# Sch1r2_1.net
KiCad netlist of a schematic drawn in EAGLE
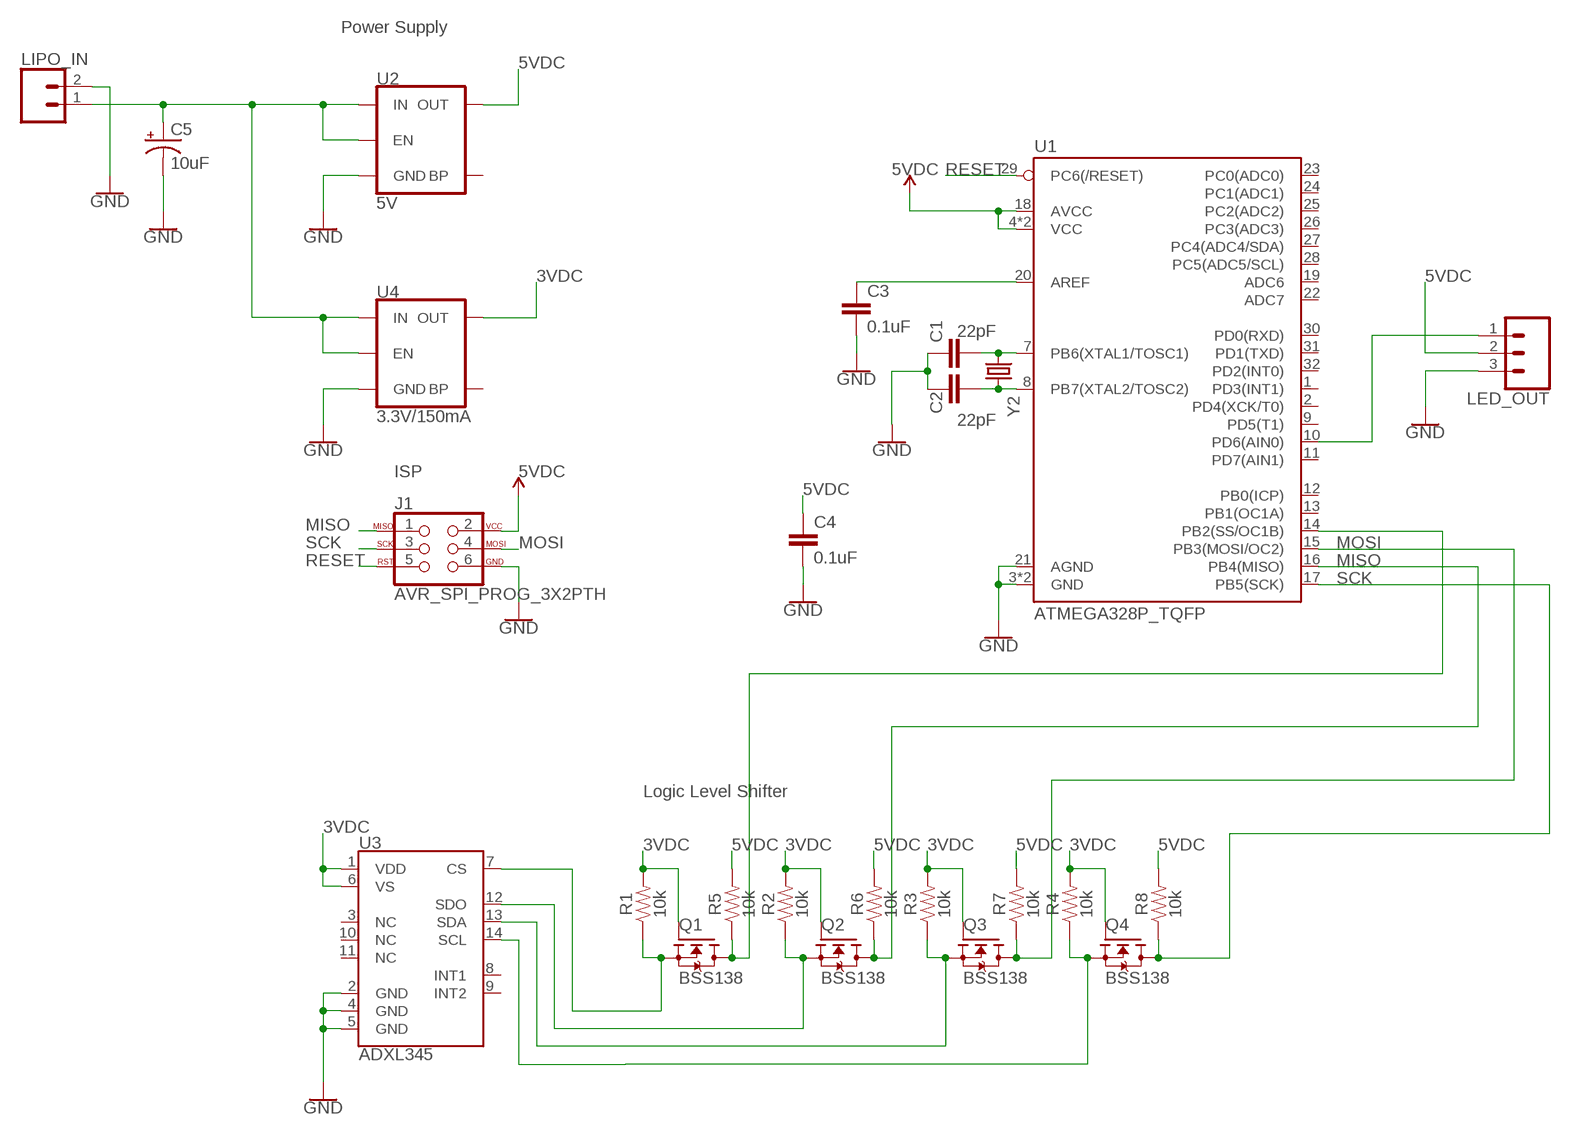
[diagram p0: schematic, sheet 1]

(export (version "E")
  (design (tool "Eeschema 10.0.6"))
  (components
    (comp (ref "C1")
      (value "22pF")
      (footprint "eagle-import:0603")
      (libsource (lib "eagle-import") (part "22PF-0603-50V-5%"))
    )
    (comp (ref "C2")
      (value "22pF")
      (footprint "eagle-import:0603")
      (libsource (lib "eagle-import") (part "22PF-0603-50V-5%"))
    )
    (comp (ref "C3")
      (value "0.1uF")
      (footprint "eagle-import:0402")
      (libsource (lib "eagle-import") (part "0.1UF-0402-16V-10%"))
    )
    (comp (ref "C4")
      (value "0.1uF")
      (footprint "eagle-import:0402")
      (libsource (lib "eagle-import") (part "0.1UF-0402-16V-10%"))
    )
    (comp (ref "C5")
      (value "10uF")
      (footprint "eagle-import:0603-POLAR")
      (libsource (lib "eagle-import") (part "10UF-POLAR-0603-6.3V-20%(TANT)"))
    )
    (comp (ref "J1")
      (value "AVR_SPI_PROG_3X2PTH")
      (footprint "eagle-import:2X3")
      (libsource (lib "eagle-import") (part "AVR_SPI_PROG_3X2PTH"))
    )
    (comp (ref "LED_OUT")
      (value "CONN_03LOCK_LONGPADS")
      (footprint "eagle-import:1X03_LOCK_LONGPADS")
      (libsource (lib "eagle-import") (part "CONN_03LOCK_LONGPADS"))
    )
    (comp (ref "LIPO_IN")
      (value "CONN_02PTH3")
      (footprint "eagle-import:1X02_LONGPADS")
      (libsource (lib "eagle-import") (part "CONN_02PTH3"))
    )
    (comp (ref "Q1")
      (value "BSS138")
      (footprint "eagle-import:SOT23")
      (fields (field (name "MF") "Fairchild"))
      (libsource (lib "eagle-import") (part "BSS138"))
    )
    (comp (ref "Q2")
      (value "BSS138")
      (footprint "eagle-import:SOT23")
      (fields (field (name "MF") "Fairchild"))
      (libsource (lib "eagle-import") (part "BSS138"))
    )
    (comp (ref "Q3")
      (value "BSS138")
      (footprint "eagle-import:SOT23")
      (fields (field (name "MF") "Fairchild"))
      (libsource (lib "eagle-import") (part "BSS138"))
    )
    (comp (ref "Q4")
      (value "BSS138")
      (footprint "eagle-import:SOT23")
      (fields (field (name "MF") "Fairchild"))
      (libsource (lib "eagle-import") (part "BSS138"))
    )
    (comp (ref "R1")
      (value "10k")
      (footprint "eagle-import:0402")
      (libsource (lib "eagle-import") (part "10KOHM-0402-1/16W-1%"))
    )
    (comp (ref "R2")
      (value "10k")
      (footprint "eagle-import:0402")
      (libsource (lib "eagle-import") (part "10KOHM-0402-1/16W-1%"))
    )
    (comp (ref "R3")
      (value "10k")
      (footprint "eagle-import:0402")
      (libsource (lib "eagle-import") (part "10KOHM-0402-1/16W-1%"))
    )
    (comp (ref "R4")
      (value "10k")
      (footprint "eagle-import:0402")
      (libsource (lib "eagle-import") (part "10KOHM-0402-1/16W-1%"))
    )
    (comp (ref "R5")
      (value "10k")
      (footprint "eagle-import:0402")
      (libsource (lib "eagle-import") (part "10KOHM-0402-1/16W-1%"))
    )
    (comp (ref "R6")
      (value "10k")
      (footprint "eagle-import:0402")
      (libsource (lib "eagle-import") (part "10KOHM-0402-1/16W-1%"))
    )
    (comp (ref "R7")
      (value "10k")
      (footprint "eagle-import:0402")
      (libsource (lib "eagle-import") (part "10KOHM-0402-1/16W-1%"))
    )
    (comp (ref "R8")
      (value "10k")
      (footprint "eagle-import:0402")
      (libsource (lib "eagle-import") (part "10KOHM-0402-1/16W-1%"))
    )
    (comp (ref "U1")
      (value "ATMEGA328P_TQFP")
      (footprint "eagle-import:TQFP32-08")
      (libsource (lib "eagle-import") (part "ATMEGA328P_TQFP"))
    )
    (comp (ref "U2")
      (value "5V")
      (footprint "eagle-import:SOT23-5")
      (libsource (lib "eagle-import") (part "V_REG_MIC52055V"))
    )
    (comp (ref "U3")
      (value "ADXL345")
      (footprint "eagle-import:LGA-14")
      (libsource (lib "eagle-import") (part "ADXL345"))
    )
    (comp (ref "U4")
      (value "3.3V/150mA")
      (footprint "eagle-import:SOT23-5")
      (libsource (lib "eagle-import") (part "V_REG_MIC52053.3V"))
    )
    (comp (ref "Y2")
      (value "CRYSTALPTH-HC49UV")
      (footprint "eagle-import:HC49U")
      (libsource (lib "eagle-import") (part "CRYSTALPTH-HC49UV"))
    )
  )
  (nets
    (net (code "1") (name "/3VDC") (class "Default")
      (node (ref "Q1") (pin "1") (pinfunction "G_1") (pintype "passive"))
      (node (ref "Q2") (pin "1") (pinfunction "G_1") (pintype "passive"))
      (node (ref "Q3") (pin "1") (pinfunction "G_1") (pintype "passive"))
      (node (ref "Q4") (pin "1") (pinfunction "G_1") (pintype "passive"))
      (node (ref "R1") (pin "2") (pinfunction "2_2") (pintype "passive"))
      (node (ref "R2") (pin "2") (pinfunction "2_2") (pintype "passive"))
      (node (ref "R3") (pin "2") (pinfunction "2_2") (pintype "passive"))
      (node (ref "R4") (pin "2") (pinfunction "2_2") (pintype "passive"))
      (node (ref "U3") (pin "1") (pinfunction "VDD_1") (pintype "bidirectional"))
      (node (ref "U3") (pin "6") (pinfunction "VS_6") (pintype "bidirectional"))
      (node (ref "U4") (pin "5") (pinfunction "OUT_5") (pintype "passive"))
    )
    (net (code "2") (name "/MISO") (class "Default")
      (node (ref "J1") (pin "1") (pinfunction "1_1") (pintype "passive"))
      (node (ref "Q2") (pin "3") (pinfunction "D_3") (pintype "passive"))
      (node (ref "R6") (pin "1") (pinfunction "1_1") (pintype "passive"))
      (node (ref "U1") (pin "16") (pinfunction "PB4(MISO)_16") (pintype "bidirectional"))
    )
    (net (code "3") (name "/MOSI") (class "Default")
      (node (ref "J1") (pin "4") (pinfunction "4_4") (pintype "passive"))
      (node (ref "Q3") (pin "3") (pinfunction "D_3") (pintype "passive"))
      (node (ref "R7") (pin "1") (pinfunction "1_1") (pintype "passive"))
      (node (ref "U1") (pin "15") (pinfunction "PB3(MOSI/OC2)_15") (pintype "bidirectional"))
    )
    (net (code "4") (name "/RESET") (class "Default")
      (node (ref "J1") (pin "5") (pinfunction "5_5") (pintype "passive"))
      (node (ref "U1") (pin "29") (pinfunction "PC6(/RESET)_29") (pintype "bidirectional"))
    )
    (net (code "5") (name "/SCK") (class "Default")
      (node (ref "J1") (pin "3") (pinfunction "3_3") (pintype "passive"))
      (node (ref "Q4") (pin "3") (pinfunction "D_3") (pintype "passive"))
      (node (ref "R8") (pin "1") (pinfunction "1_1") (pintype "passive"))
      (node (ref "U1") (pin "17") (pinfunction "PB5(SCK)_17") (pintype "bidirectional"))
    )
    (net (code "6") (name "GND") (class "Default")
      (node (ref "C1") (pin "1") (pinfunction "1_1") (pintype "passive"))
      (node (ref "C2") (pin "1") (pinfunction "1_1") (pintype "passive"))
      (node (ref "C3") (pin "2") (pinfunction "2_2") (pintype "passive"))
      (node (ref "C4") (pin "2") (pinfunction "2_2") (pintype "passive"))
      (node (ref "C5") (pin "-") (pinfunction "-_-") (pintype "passive"))
      (node (ref "J1") (pin "6") (pinfunction "6_6") (pintype "passive"))
      (node (ref "LED_OUT") (pin "3") (pinfunction "3_3") (pintype "passive"))
      (node (ref "LIPO_IN") (pin "2") (pinfunction "2_2") (pintype "passive"))
      (node (ref "U1") (pin "21") (pinfunction "AGND_21") (pintype "bidirectional"))
      (node (ref "U1") (pin "3") (pinfunction "GND_3") (pintype "bidirectional"))
      (node (ref "U1") (pin "5") (pinfunction "GND_5") (pintype "bidirectional"))
      (node (ref "U2") (pin "2") (pinfunction "GND_2") (pintype "input"))
      (node (ref "U3") (pin "2") (pinfunction "GND_2") (pintype "bidirectional"))
      (node (ref "U3") (pin "4") (pinfunction "GND_4") (pintype "bidirectional"))
      (node (ref "U3") (pin "5") (pinfunction "GND_5") (pintype "bidirectional"))
      (node (ref "U4") (pin "2") (pinfunction "GND_2") (pintype "input"))
    )
    (net (code "7") (name "Net-(Q1-D)") (class "Default")
      (node (ref "Q1") (pin "3") (pinfunction "D_3") (pintype "passive"))
      (node (ref "R5") (pin "1") (pinfunction "1_1") (pintype "passive"))
      (node (ref "U1") (pin "14") (pinfunction "PB2(SS/OC1B)_14") (pintype "bidirectional"))
    )
    (net (code "8") (name "Net-(Q1-S)") (class "Default")
      (node (ref "Q1") (pin "2") (pinfunction "S_2") (pintype "passive"))
      (node (ref "R1") (pin "1") (pinfunction "1_1") (pintype "passive"))
      (node (ref "U3") (pin "7") (pinfunction "CS_7") (pintype "bidirectional"))
    )
    (net (code "9") (name "Net-(Q2-S)") (class "Default")
      (node (ref "Q2") (pin "2") (pinfunction "S_2") (pintype "passive"))
      (node (ref "R2") (pin "1") (pinfunction "1_1") (pintype "passive"))
      (node (ref "U3") (pin "12") (pinfunction "SDO_12") (pintype "bidirectional"))
    )
    (net (code "10") (name "Net-(Q3-S)") (class "Default")
      (node (ref "Q3") (pin "2") (pinfunction "S_2") (pintype "passive"))
      (node (ref "R3") (pin "1") (pinfunction "1_1") (pintype "passive"))
      (node (ref "U3") (pin "13") (pinfunction "SDA_13") (pintype "bidirectional"))
    )
    (net (code "11") (name "Net-(Q4-S)") (class "Default")
      (node (ref "Q4") (pin "2") (pinfunction "S_2") (pintype "passive"))
      (node (ref "R4") (pin "1") (pinfunction "1_1") (pintype "passive"))
      (node (ref "U3") (pin "14") (pinfunction "SCL_14") (pintype "bidirectional"))
    )
    (net (code "12") (name "Net-(U1-AREF)") (class "Default")
      (node (ref "C3") (pin "1") (pinfunction "1_1") (pintype "passive"))
      (node (ref "U1") (pin "20") (pinfunction "AREF_20") (pintype "bidirectional"))
    )
    (net (code "13") (name "Net-(U1-PB6(XTAL1{slash}TOSC1))") (class "Default")
      (node (ref "C1") (pin "2") (pinfunction "2_2") (pintype "passive"))
      (node (ref "U1") (pin "7") (pinfunction "PB6(XTAL1/TOSC1)_7") (pintype "bidirectional"))
      (node (ref "Y2") (pin "2") (pinfunction "2_2") (pintype "passive"))
    )
    (net (code "14") (name "Net-(U1-PB7(XTAL2{slash}TOSC2))") (class "Default")
      (node (ref "C2") (pin "2") (pinfunction "2_2") (pintype "passive"))
      (node (ref "U1") (pin "8") (pinfunction "PB7(XTAL2/TOSC2)_8") (pintype "bidirectional"))
      (node (ref "Y2") (pin "1") (pinfunction "1_1") (pintype "passive"))
    )
    (net (code "15") (name "Net-(U1-PD6(AIN0))") (class "Default")
      (node (ref "LED_OUT") (pin "1") (pinfunction "1_1") (pintype "passive"))
      (node (ref "U1") (pin "10") (pinfunction "PD6(AIN0)_10") (pintype "bidirectional"))
    )
    (net (code "16") (name "Net-(U2-EN)") (class "Default")
      (node (ref "C5") (pin "+") (pinfunction "+_+") (pintype "passive"))
      (node (ref "LIPO_IN") (pin "1") (pinfunction "1_1") (pintype "passive"))
      (node (ref "U2") (pin "1") (pinfunction "IN_1") (pintype "input"))
      (node (ref "U2") (pin "3") (pinfunction "EN_3") (pintype "input"))
      (node (ref "U4") (pin "1") (pinfunction "IN_1") (pintype "input"))
      (node (ref "U4") (pin "3") (pinfunction "EN_3") (pintype "input"))
    )
    (net (code "17") (name "VCC") (class "Default")
      (node (ref "C4") (pin "1") (pinfunction "1_1") (pintype "passive"))
      (node (ref "J1") (pin "2") (pinfunction "2_2") (pintype "passive"))
      (node (ref "LED_OUT") (pin "2") (pinfunction "2_2") (pintype "passive"))
      (node (ref "R5") (pin "2") (pinfunction "2_2") (pintype "passive"))
      (node (ref "R6") (pin "2") (pinfunction "2_2") (pintype "passive"))
      (node (ref "R7") (pin "2") (pinfunction "2_2") (pintype "passive"))
      (node (ref "R8") (pin "2") (pinfunction "2_2") (pintype "passive"))
      (node (ref "U1") (pin "18") (pinfunction "AVCC_18") (pintype "bidirectional"))
      (node (ref "U1") (pin "4") (pinfunction "VCC_4") (pintype "bidirectional"))
      (node (ref "U1") (pin "6") (pinfunction "VCC_6") (pintype "bidirectional"))
      (node (ref "U2") (pin "5") (pinfunction "OUT_5") (pintype "passive"))
    )
    (net (code "18") (name "unconnected-(U1-ADC6-Pad19)") (class "Default")
      (node (ref "U1") (pin "19") (pinfunction "ADC6_19") (pintype "bidirectional"))
    )
    (net (code "19") (name "unconnected-(U1-ADC7-Pad22)") (class "Default")
      (node (ref "U1") (pin "22") (pinfunction "ADC7_22") (pintype "bidirectional"))
    )
    (net (code "20") (name "unconnected-(U1-PB0(ICP)-Pad12)") (class "Default")
      (node (ref "U1") (pin "12") (pinfunction "PB0(ICP)_12") (pintype "bidirectional"))
    )
    (net (code "21") (name "unconnected-(U1-PB1(OC1A)-Pad13)") (class "Default")
      (node (ref "U1") (pin "13") (pinfunction "PB1(OC1A)_13") (pintype "bidirectional"))
    )
    (net (code "22") (name "unconnected-(U1-PC0(ADC0)-Pad23)") (class "Default")
      (node (ref "U1") (pin "23") (pinfunction "PC0(ADC0)_23") (pintype "bidirectional"))
    )
    (net (code "23") (name "unconnected-(U1-PC1(ADC1)-Pad24)") (class "Default")
      (node (ref "U1") (pin "24") (pinfunction "PC1(ADC1)_24") (pintype "bidirectional"))
    )
    (net (code "24") (name "unconnected-(U1-PC2(ADC2)-Pad25)") (class "Default")
      (node (ref "U1") (pin "25") (pinfunction "PC2(ADC2)_25") (pintype "bidirectional"))
    )
    (net (code "25") (name "unconnected-(U1-PC3(ADC3)-Pad26)") (class "Default")
      (node (ref "U1") (pin "26") (pinfunction "PC3(ADC3)_26") (pintype "bidirectional"))
    )
    (net (code "26") (name "unconnected-(U1-PC4(ADC4{slash}SDA)-Pad27)") (class "Default")
      (node (ref "U1") (pin "27") (pinfunction "PC4(ADC4/SDA)_27") (pintype "bidirectional"))
    )
    (net (code "27") (name "unconnected-(U1-PC5(ADC5{slash}SCL)-Pad28)") (class "Default")
      (node (ref "U1") (pin "28") (pinfunction "PC5(ADC5/SCL)_28") (pintype "bidirectional"))
    )
    (net (code "28") (name "unconnected-(U1-PD0(RXD)-Pad30)") (class "Default")
      (node (ref "U1") (pin "30") (pinfunction "PD0(RXD)_30") (pintype "bidirectional"))
    )
    (net (code "29") (name "unconnected-(U1-PD1(TXD)-Pad31)") (class "Default")
      (node (ref "U1") (pin "31") (pinfunction "PD1(TXD)_31") (pintype "bidirectional"))
    )
    (net (code "30") (name "unconnected-(U1-PD2(INT0)-Pad32)") (class "Default")
      (node (ref "U1") (pin "32") (pinfunction "PD2(INT0)_32") (pintype "bidirectional"))
    )
    (net (code "31") (name "unconnected-(U1-PD3(INT1)-Pad1)") (class "Default")
      (node (ref "U1") (pin "1") (pinfunction "PD3(INT1)_1") (pintype "bidirectional"))
    )
    (net (code "32") (name "unconnected-(U1-PD4(XCK{slash}T0)-Pad2)") (class "Default")
      (node (ref "U1") (pin "2") (pinfunction "PD4(XCK/T0)_2") (pintype "bidirectional"))
    )
    (net (code "33") (name "unconnected-(U1-PD5(T1)-Pad9)") (class "Default")
      (node (ref "U1") (pin "9") (pinfunction "PD5(T1)_9") (pintype "bidirectional"))
    )
    (net (code "34") (name "unconnected-(U1-PD7(AIN1)-Pad11)") (class "Default")
      (node (ref "U1") (pin "11") (pinfunction "PD7(AIN1)_11") (pintype "bidirectional"))
    )
    (net (code "35") (name "unconnected-(U2-BP-Pad4)") (class "Default")
      (node (ref "U2") (pin "4") (pinfunction "BP_4") (pintype "input"))
    )
    (net (code "36") (name "unconnected-(U3-INT1-Pad8)") (class "Default")
      (node (ref "U3") (pin "8") (pinfunction "INT1_8") (pintype "bidirectional"))
    )
    (net (code "37") (name "unconnected-(U3-INT2-Pad9)") (class "Default")
      (node (ref "U3") (pin "9") (pinfunction "INT2_9") (pintype "bidirectional"))
    )
    (net (code "38") (name "unconnected-(U3-NC-Pad3)") (class "Default")
      (node (ref "U3") (pin "3") (pinfunction "NC_3") (pintype "bidirectional"))
    )
    (net (code "39") (name "unconnected-(U3-NC-Pad10)") (class "Default")
      (node (ref "U3") (pin "10") (pinfunction "NC_10") (pintype "bidirectional"))
    )
    (net (code "40") (name "unconnected-(U3-NC-Pad11)") (class "Default")
      (node (ref "U3") (pin "11") (pinfunction "NC_11") (pintype "bidirectional"))
    )
    (net (code "41") (name "unconnected-(U4-BP-Pad4)") (class "Default")
      (node (ref "U4") (pin "4") (pinfunction "BP_4") (pintype "input"))
    )
  )
)
